# 4_-_Output.net
KiCad netlist of a schematic drawn in Altium Designer
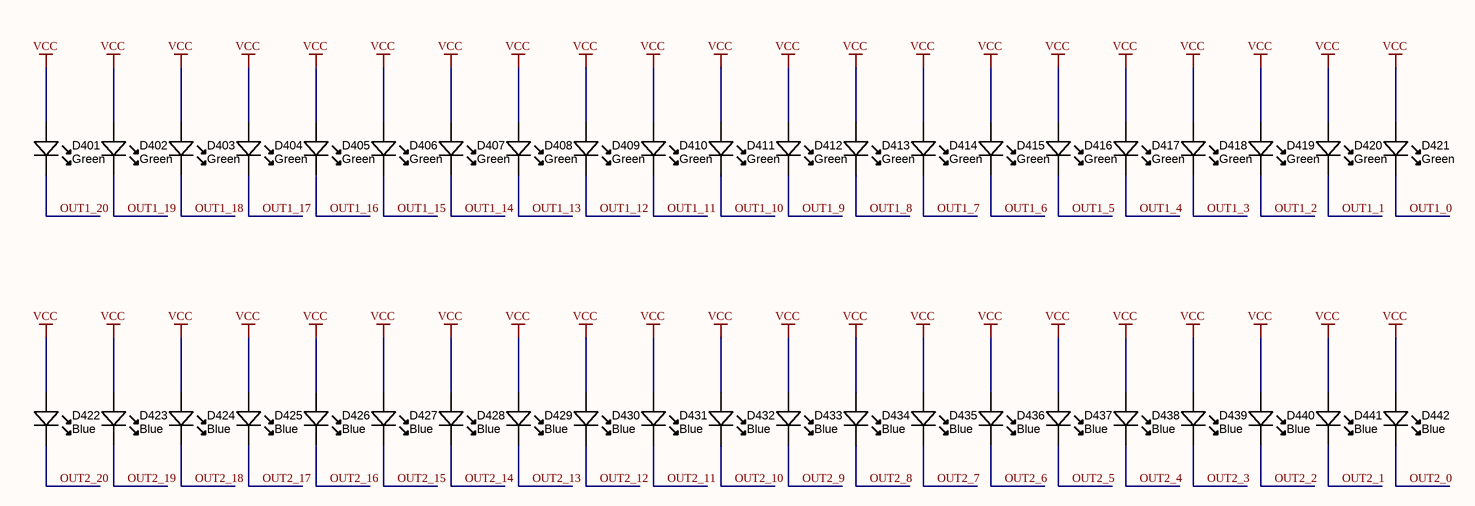
[diagram p0: 4 - Output.SchDoc]

(export (version "E")
  (design (tool "Eeschema 10.0.6"))
  (components
    (comp (ref "D401")
      (value "Green")
      (footprint "LED-0805S-SIDELED-2.1X0.6X1.0")
      (description "LED 0805 SIDELED SMD Green 250mcd 525nm")
      (fields (field (name "COLOR") "Green"))
      (libsource (lib "PBL - Light Sources") (part "LED_SMD_PureGreen_0805RA_250mcd"))
    )
    (comp (ref "D402")
      (value "Green")
      (footprint "LED-0805S-SIDELED-2.1X0.6X1.0")
      (description "LED 0805 SIDELED SMD Green 250mcd 525nm")
      (fields (field (name "COLOR") "Green"))
      (libsource (lib "PBL - Light Sources") (part "LED_SMD_PureGreen_0805RA_250mcd"))
    )
    (comp (ref "D403")
      (value "Green")
      (footprint "LED-0805S-SIDELED-2.1X0.6X1.0")
      (description "LED 0805 SIDELED SMD Green 250mcd 525nm")
      (fields (field (name "COLOR") "Green"))
      (libsource (lib "PBL - Light Sources") (part "LED_SMD_PureGreen_0805RA_250mcd"))
    )
    (comp (ref "D404")
      (value "Green")
      (footprint "LED-0805S-SIDELED-2.1X0.6X1.0")
      (description "LED 0805 SIDELED SMD Green 250mcd 525nm")
      (fields (field (name "COLOR") "Green"))
      (libsource (lib "PBL - Light Sources") (part "LED_SMD_PureGreen_0805RA_250mcd"))
    )
    (comp (ref "D405")
      (value "Green")
      (footprint "LED-0805S-SIDELED-2.1X0.6X1.0")
      (description "LED 0805 SIDELED SMD Green 250mcd 525nm")
      (fields (field (name "COLOR") "Green"))
      (libsource (lib "PBL - Light Sources") (part "LED_SMD_PureGreen_0805RA_250mcd"))
    )
    (comp (ref "D406")
      (value "Green")
      (footprint "LED-0805S-SIDELED-2.1X0.6X1.0")
      (description "LED 0805 SIDELED SMD Green 250mcd 525nm")
      (fields (field (name "COLOR") "Green"))
      (libsource (lib "PBL - Light Sources") (part "LED_SMD_PureGreen_0805RA_250mcd"))
    )
    (comp (ref "D407")
      (value "Green")
      (footprint "LED-0805S-SIDELED-2.1X0.6X1.0")
      (description "LED 0805 SIDELED SMD Green 250mcd 525nm")
      (fields (field (name "COLOR") "Green"))
      (libsource (lib "PBL - Light Sources") (part "LED_SMD_PureGreen_0805RA_250mcd"))
    )
    (comp (ref "D408")
      (value "Green")
      (footprint "LED-0805S-SIDELED-2.1X0.6X1.0")
      (description "LED 0805 SIDELED SMD Green 250mcd 525nm")
      (fields (field (name "COLOR") "Green"))
      (libsource (lib "PBL - Light Sources") (part "LED_SMD_PureGreen_0805RA_250mcd"))
    )
    (comp (ref "D409")
      (value "Green")
      (footprint "LED-0805S-SIDELED-2.1X0.6X1.0")
      (description "LED 0805 SIDELED SMD Green 250mcd 525nm")
      (fields (field (name "COLOR") "Green"))
      (libsource (lib "PBL - Light Sources") (part "LED_SMD_PureGreen_0805RA_250mcd"))
    )
    (comp (ref "D410")
      (value "Green")
      (footprint "LED-0805S-SIDELED-2.1X0.6X1.0")
      (description "LED 0805 SIDELED SMD Green 250mcd 525nm")
      (fields (field (name "COLOR") "Green"))
      (libsource (lib "PBL - Light Sources") (part "LED_SMD_PureGreen_0805RA_250mcd"))
    )
    (comp (ref "D411")
      (value "Green")
      (footprint "LED-0805S-SIDELED-2.1X0.6X1.0")
      (description "LED 0805 SIDELED SMD Green 250mcd 525nm")
      (fields (field (name "COLOR") "Green"))
      (libsource (lib "PBL - Light Sources") (part "LED_SMD_PureGreen_0805RA_250mcd"))
    )
    (comp (ref "D412")
      (value "Green")
      (footprint "LED-0805S-SIDELED-2.1X0.6X1.0")
      (description "LED 0805 SIDELED SMD Green 250mcd 525nm")
      (fields (field (name "COLOR") "Green"))
      (libsource (lib "PBL - Light Sources") (part "LED_SMD_PureGreen_0805RA_250mcd"))
    )
    (comp (ref "D413")
      (value "Green")
      (footprint "LED-0805S-SIDELED-2.1X0.6X1.0")
      (description "LED 0805 SIDELED SMD Green 250mcd 525nm")
      (fields (field (name "COLOR") "Green"))
      (libsource (lib "PBL - Light Sources") (part "LED_SMD_PureGreen_0805RA_250mcd"))
    )
    (comp (ref "D414")
      (value "Green")
      (footprint "LED-0805S-SIDELED-2.1X0.6X1.0")
      (description "LED 0805 SIDELED SMD Green 250mcd 525nm")
      (fields (field (name "COLOR") "Green"))
      (libsource (lib "PBL - Light Sources") (part "LED_SMD_PureGreen_0805RA_250mcd"))
    )
    (comp (ref "D415")
      (value "Green")
      (footprint "LED-0805S-SIDELED-2.1X0.6X1.0")
      (description "LED 0805 SIDELED SMD Green 250mcd 525nm")
      (fields (field (name "COLOR") "Green"))
      (libsource (lib "PBL - Light Sources") (part "LED_SMD_PureGreen_0805RA_250mcd"))
    )
    (comp (ref "D416")
      (value "Green")
      (footprint "LED-0805S-SIDELED-2.1X0.6X1.0")
      (description "LED 0805 SIDELED SMD Green 250mcd 525nm")
      (fields (field (name "COLOR") "Green"))
      (libsource (lib "PBL - Light Sources") (part "LED_SMD_PureGreen_0805RA_250mcd"))
    )
    (comp (ref "D417")
      (value "Green")
      (footprint "LED-0805S-SIDELED-2.1X0.6X1.0")
      (description "LED 0805 SIDELED SMD Green 250mcd 525nm")
      (fields (field (name "COLOR") "Green"))
      (libsource (lib "PBL - Light Sources") (part "LED_SMD_PureGreen_0805RA_250mcd"))
    )
    (comp (ref "D418")
      (value "Green")
      (footprint "LED-0805S-SIDELED-2.1X0.6X1.0")
      (description "LED 0805 SIDELED SMD Green 250mcd 525nm")
      (fields (field (name "COLOR") "Green"))
      (libsource (lib "PBL - Light Sources") (part "LED_SMD_PureGreen_0805RA_250mcd"))
    )
    (comp (ref "D419")
      (value "Green")
      (footprint "LED-0805S-SIDELED-2.1X0.6X1.0")
      (description "LED 0805 SIDELED SMD Green 250mcd 525nm")
      (fields (field (name "COLOR") "Green"))
      (libsource (lib "PBL - Light Sources") (part "LED_SMD_PureGreen_0805RA_250mcd"))
    )
    (comp (ref "D420")
      (value "Green")
      (footprint "LED-0805S-SIDELED-2.1X0.6X1.0")
      (description "LED 0805 SIDELED SMD Green 250mcd 525nm")
      (fields (field (name "COLOR") "Green"))
      (libsource (lib "PBL - Light Sources") (part "LED_SMD_PureGreen_0805RA_250mcd"))
    )
    (comp (ref "D421")
      (value "Green")
      (footprint "LED-0805S-SIDELED-2.1X0.6X1.0")
      (description "LED 0805 SIDELED SMD Green 250mcd 525nm")
      (fields (field (name "COLOR") "Green"))
      (libsource (lib "PBL - Light Sources") (part "LED_SMD_PureGreen_0805RA_250mcd"))
    )
    (comp (ref "D422")
      (value "Blue")
      (footprint "LED-0805S-SIDELED-2.1X0.6X1.0")
      (description "LED 0805 SIDELED SMD Green 250mcd 525nm")
      (fields (field (name "COLOR") "Blue"))
      (libsource (lib "PBL - Light Sources") (part "LED_SMD_PureGreen_0805RA_250mcd"))
    )
    (comp (ref "D423")
      (value "Blue")
      (footprint "LED-0805S-SIDELED-2.1X0.6X1.0")
      (description "LED 0805 SIDELED SMD Green 250mcd 525nm")
      (fields (field (name "COLOR") "Blue"))
      (libsource (lib "PBL - Light Sources") (part "LED_SMD_PureGreen_0805RA_250mcd"))
    )
    (comp (ref "D424")
      (value "Blue")
      (footprint "LED-0805S-SIDELED-2.1X0.6X1.0")
      (description "LED 0805 SIDELED SMD Green 250mcd 525nm")
      (fields (field (name "COLOR") "Blue"))
      (libsource (lib "PBL - Light Sources") (part "LED_SMD_PureGreen_0805RA_250mcd"))
    )
    (comp (ref "D425")
      (value "Blue")
      (footprint "LED-0805S-SIDELED-2.1X0.6X1.0")
      (description "LED 0805 SIDELED SMD Green 250mcd 525nm")
      (fields (field (name "COLOR") "Blue"))
      (libsource (lib "PBL - Light Sources") (part "LED_SMD_PureGreen_0805RA_250mcd"))
    )
    (comp (ref "D426")
      (value "Blue")
      (footprint "LED-0805S-SIDELED-2.1X0.6X1.0")
      (description "LED 0805 SIDELED SMD Green 250mcd 525nm")
      (fields (field (name "COLOR") "Blue"))
      (libsource (lib "PBL - Light Sources") (part "LED_SMD_PureGreen_0805RA_250mcd"))
    )
    (comp (ref "D427")
      (value "Blue")
      (footprint "LED-0805S-SIDELED-2.1X0.6X1.0")
      (description "LED 0805 SIDELED SMD Green 250mcd 525nm")
      (fields (field (name "COLOR") "Blue"))
      (libsource (lib "PBL - Light Sources") (part "LED_SMD_PureGreen_0805RA_250mcd"))
    )
    (comp (ref "D428")
      (value "Blue")
      (footprint "LED-0805S-SIDELED-2.1X0.6X1.0")
      (description "LED 0805 SIDELED SMD Green 250mcd 525nm")
      (fields (field (name "COLOR") "Blue"))
      (libsource (lib "PBL - Light Sources") (part "LED_SMD_PureGreen_0805RA_250mcd"))
    )
    (comp (ref "D429")
      (value "Blue")
      (footprint "LED-0805S-SIDELED-2.1X0.6X1.0")
      (description "LED 0805 SIDELED SMD Green 250mcd 525nm")
      (fields (field (name "COLOR") "Blue"))
      (libsource (lib "PBL - Light Sources") (part "LED_SMD_PureGreen_0805RA_250mcd"))
    )
    (comp (ref "D430")
      (value "Blue")
      (footprint "LED-0805S-SIDELED-2.1X0.6X1.0")
      (description "LED 0805 SIDELED SMD Green 250mcd 525nm")
      (fields (field (name "COLOR") "Blue"))
      (libsource (lib "PBL - Light Sources") (part "LED_SMD_PureGreen_0805RA_250mcd"))
    )
    (comp (ref "D431")
      (value "Blue")
      (footprint "LED-0805S-SIDELED-2.1X0.6X1.0")
      (description "LED 0805 SIDELED SMD Green 250mcd 525nm")
      (fields (field (name "COLOR") "Blue"))
      (libsource (lib "PBL - Light Sources") (part "LED_SMD_PureGreen_0805RA_250mcd"))
    )
    (comp (ref "D432")
      (value "Blue")
      (footprint "LED-0805S-SIDELED-2.1X0.6X1.0")
      (description "LED 0805 SIDELED SMD Green 250mcd 525nm")
      (fields (field (name "COLOR") "Blue"))
      (libsource (lib "PBL - Light Sources") (part "LED_SMD_PureGreen_0805RA_250mcd"))
    )
    (comp (ref "D433")
      (value "Blue")
      (footprint "LED-0805S-SIDELED-2.1X0.6X1.0")
      (description "LED 0805 SIDELED SMD Green 250mcd 525nm")
      (fields (field (name "COLOR") "Blue"))
      (libsource (lib "PBL - Light Sources") (part "LED_SMD_PureGreen_0805RA_250mcd"))
    )
    (comp (ref "D434")
      (value "Blue")
      (footprint "LED-0805S-SIDELED-2.1X0.6X1.0")
      (description "LED 0805 SIDELED SMD Green 250mcd 525nm")
      (fields (field (name "COLOR") "Blue"))
      (libsource (lib "PBL - Light Sources") (part "LED_SMD_PureGreen_0805RA_250mcd"))
    )
    (comp (ref "D435")
      (value "Blue")
      (footprint "LED-0805S-SIDELED-2.1X0.6X1.0")
      (description "LED 0805 SIDELED SMD Green 250mcd 525nm")
      (fields (field (name "COLOR") "Blue"))
      (libsource (lib "PBL - Light Sources") (part "LED_SMD_PureGreen_0805RA_250mcd"))
    )
    (comp (ref "D436")
      (value "Blue")
      (footprint "LED-0805S-SIDELED-2.1X0.6X1.0")
      (description "LED 0805 SIDELED SMD Green 250mcd 525nm")
      (fields (field (name "COLOR") "Blue"))
      (libsource (lib "PBL - Light Sources") (part "LED_SMD_PureGreen_0805RA_250mcd"))
    )
    (comp (ref "D437")
      (value "Blue")
      (footprint "LED-0805S-SIDELED-2.1X0.6X1.0")
      (description "LED 0805 SIDELED SMD Green 250mcd 525nm")
      (fields (field (name "COLOR") "Blue"))
      (libsource (lib "PBL - Light Sources") (part "LED_SMD_PureGreen_0805RA_250mcd"))
    )
    (comp (ref "D438")
      (value "Blue")
      (footprint "LED-0805S-SIDELED-2.1X0.6X1.0")
      (description "LED 0805 SIDELED SMD Green 250mcd 525nm")
      (fields (field (name "COLOR") "Blue"))
      (libsource (lib "PBL - Light Sources") (part "LED_SMD_PureGreen_0805RA_250mcd"))
    )
    (comp (ref "D439")
      (value "Blue")
      (footprint "LED-0805S-SIDELED-2.1X0.6X1.0")
      (description "LED 0805 SIDELED SMD Green 250mcd 525nm")
      (fields (field (name "COLOR") "Blue"))
      (libsource (lib "PBL - Light Sources") (part "LED_SMD_PureGreen_0805RA_250mcd"))
    )
    (comp (ref "D440")
      (value "Blue")
      (footprint "LED-0805S-SIDELED-2.1X0.6X1.0")
      (description "LED 0805 SIDELED SMD Green 250mcd 525nm")
      (fields (field (name "COLOR") "Blue"))
      (libsource (lib "PBL - Light Sources") (part "LED_SMD_PureGreen_0805RA_250mcd"))
    )
    (comp (ref "D441")
      (value "Blue")
      (footprint "LED-0805S-SIDELED-2.1X0.6X1.0")
      (description "LED 0805 SIDELED SMD Green 250mcd 525nm")
      (fields (field (name "COLOR") "Blue"))
      (libsource (lib "PBL - Light Sources") (part "LED_SMD_PureGreen_0805RA_250mcd"))
    )
    (comp (ref "D442")
      (value "Blue")
      (footprint "LED-0805S-SIDELED-2.1X0.6X1.0")
      (description "LED 0805 SIDELED SMD Green 250mcd 525nm")
      (fields (field (name "COLOR") "Blue"))
      (libsource (lib "PBL - Light Sources") (part "LED_SMD_PureGreen_0805RA_250mcd"))
    )
  )
  (nets
    (net (code "1") (name "/OUT1_0") (class "Default")
      (node (ref "D421") (pin "K") (pinfunction "K_K") (pintype "passive"))
    )
    (net (code "2") (name "/OUT1_1") (class "Default")
      (node (ref "D420") (pin "K") (pinfunction "K_K") (pintype "passive"))
    )
    (net (code "3") (name "/OUT1_2") (class "Default")
      (node (ref "D419") (pin "K") (pinfunction "K_K") (pintype "passive"))
    )
    (net (code "4") (name "/OUT1_3") (class "Default")
      (node (ref "D418") (pin "K") (pinfunction "K_K") (pintype "passive"))
    )
    (net (code "5") (name "/OUT1_4") (class "Default")
      (node (ref "D417") (pin "K") (pinfunction "K_K") (pintype "passive"))
    )
    (net (code "6") (name "/OUT1_5") (class "Default")
      (node (ref "D416") (pin "K") (pinfunction "K_K") (pintype "passive"))
    )
    (net (code "7") (name "/OUT1_6") (class "Default")
      (node (ref "D415") (pin "K") (pinfunction "K_K") (pintype "passive"))
    )
    (net (code "8") (name "/OUT1_7") (class "Default")
      (node (ref "D414") (pin "K") (pinfunction "K_K") (pintype "passive"))
    )
    (net (code "9") (name "/OUT1_8") (class "Default")
      (node (ref "D413") (pin "K") (pinfunction "K_K") (pintype "passive"))
    )
    (net (code "10") (name "/OUT1_9") (class "Default")
      (node (ref "D412") (pin "K") (pinfunction "K_K") (pintype "passive"))
    )
    (net (code "11") (name "/OUT1_10") (class "Default")
      (node (ref "D411") (pin "K") (pinfunction "K_K") (pintype "passive"))
    )
    (net (code "12") (name "/OUT1_11") (class "Default")
      (node (ref "D410") (pin "K") (pinfunction "K_K") (pintype "passive"))
    )
    (net (code "13") (name "/OUT1_12") (class "Default")
      (node (ref "D409") (pin "K") (pinfunction "K_K") (pintype "passive"))
    )
    (net (code "14") (name "/OUT1_13") (class "Default")
      (node (ref "D408") (pin "K") (pinfunction "K_K") (pintype "passive"))
    )
    (net (code "15") (name "/OUT1_14") (class "Default")
      (node (ref "D407") (pin "K") (pinfunction "K_K") (pintype "passive"))
    )
    (net (code "16") (name "/OUT1_15") (class "Default")
      (node (ref "D406") (pin "K") (pinfunction "K_K") (pintype "passive"))
    )
    (net (code "17") (name "/OUT1_16") (class "Default")
      (node (ref "D405") (pin "K") (pinfunction "K_K") (pintype "passive"))
    )
    (net (code "18") (name "/OUT1_17") (class "Default")
      (node (ref "D404") (pin "K") (pinfunction "K_K") (pintype "passive"))
    )
    (net (code "19") (name "/OUT1_18") (class "Default")
      (node (ref "D403") (pin "K") (pinfunction "K_K") (pintype "passive"))
    )
    (net (code "20") (name "/OUT1_19") (class "Default")
      (node (ref "D402") (pin "K") (pinfunction "K_K") (pintype "passive"))
    )
    (net (code "21") (name "/OUT1_20") (class "Default")
      (node (ref "D401") (pin "K") (pinfunction "K_K") (pintype "passive"))
    )
    (net (code "22") (name "/OUT2_0") (class "Default")
      (node (ref "D442") (pin "K") (pinfunction "K_K") (pintype "passive"))
    )
    (net (code "23") (name "/OUT2_1") (class "Default")
      (node (ref "D441") (pin "K") (pinfunction "K_K") (pintype "passive"))
    )
    (net (code "24") (name "/OUT2_2") (class "Default")
      (node (ref "D440") (pin "K") (pinfunction "K_K") (pintype "passive"))
    )
    (net (code "25") (name "/OUT2_3") (class "Default")
      (node (ref "D439") (pin "K") (pinfunction "K_K") (pintype "passive"))
    )
    (net (code "26") (name "/OUT2_4") (class "Default")
      (node (ref "D438") (pin "K") (pinfunction "K_K") (pintype "passive"))
    )
    (net (code "27") (name "/OUT2_5") (class "Default")
      (node (ref "D437") (pin "K") (pinfunction "K_K") (pintype "passive"))
    )
    (net (code "28") (name "/OUT2_6") (class "Default")
      (node (ref "D436") (pin "K") (pinfunction "K_K") (pintype "passive"))
    )
    (net (code "29") (name "/OUT2_7") (class "Default")
      (node (ref "D435") (pin "K") (pinfunction "K_K") (pintype "passive"))
    )
    (net (code "30") (name "/OUT2_8") (class "Default")
      (node (ref "D434") (pin "K") (pinfunction "K_K") (pintype "passive"))
    )
    (net (code "31") (name "/OUT2_9") (class "Default")
      (node (ref "D433") (pin "K") (pinfunction "K_K") (pintype "passive"))
    )
    (net (code "32") (name "/OUT2_10") (class "Default")
      (node (ref "D432") (pin "K") (pinfunction "K_K") (pintype "passive"))
    )
    (net (code "33") (name "/OUT2_11") (class "Default")
      (node (ref "D431") (pin "K") (pinfunction "K_K") (pintype "passive"))
    )
    (net (code "34") (name "/OUT2_12") (class "Default")
      (node (ref "D430") (pin "K") (pinfunction "K_K") (pintype "passive"))
    )
    (net (code "35") (name "/OUT2_13") (class "Default")
      (node (ref "D429") (pin "K") (pinfunction "K_K") (pintype "passive"))
    )
    (net (code "36") (name "/OUT2_14") (class "Default")
      (node (ref "D428") (pin "K") (pinfunction "K_K") (pintype "passive"))
    )
    (net (code "37") (name "/OUT2_15") (class "Default")
      (node (ref "D427") (pin "K") (pinfunction "K_K") (pintype "passive"))
    )
    (net (code "38") (name "/OUT2_16") (class "Default")
      (node (ref "D426") (pin "K") (pinfunction "K_K") (pintype "passive"))
    )
    (net (code "39") (name "/OUT2_17") (class "Default")
      (node (ref "D425") (pin "K") (pinfunction "K_K") (pintype "passive"))
    )
    (net (code "40") (name "/OUT2_18") (class "Default")
      (node (ref "D424") (pin "K") (pinfunction "K_K") (pintype "passive"))
    )
    (net (code "41") (name "/OUT2_19") (class "Default")
      (node (ref "D423") (pin "K") (pinfunction "K_K") (pintype "passive"))
    )
    (net (code "42") (name "/OUT2_20") (class "Default")
      (node (ref "D422") (pin "K") (pinfunction "K_K") (pintype "passive"))
    )
    (net (code "43") (name "VCC") (class "Default")
      (node (ref "D401") (pin "A") (pinfunction "A_A") (pintype "passive"))
      (node (ref "D402") (pin "A") (pinfunction "A_A") (pintype "passive"))
      (node (ref "D403") (pin "A") (pinfunction "A_A") (pintype "passive"))
      (node (ref "D404") (pin "A") (pinfunction "A_A") (pintype "passive"))
      (node (ref "D405") (pin "A") (pinfunction "A_A") (pintype "passive"))
      (node (ref "D406") (pin "A") (pinfunction "A_A") (pintype "passive"))
      (node (ref "D407") (pin "A") (pinfunction "A_A") (pintype "passive"))
      (node (ref "D408") (pin "A") (pinfunction "A_A") (pintype "passive"))
      (node (ref "D409") (pin "A") (pinfunction "A_A") (pintype "passive"))
      (node (ref "D410") (pin "A") (pinfunction "A_A") (pintype "passive"))
      (node (ref "D411") (pin "A") (pinfunction "A_A") (pintype "passive"))
      (node (ref "D412") (pin "A") (pinfunction "A_A") (pintype "passive"))
      (node (ref "D413") (pin "A") (pinfunction "A_A") (pintype "passive"))
      (node (ref "D414") (pin "A") (pinfunction "A_A") (pintype "passive"))
      (node (ref "D415") (pin "A") (pinfunction "A_A") (pintype "passive"))
      (node (ref "D416") (pin "A") (pinfunction "A_A") (pintype "passive"))
      (node (ref "D417") (pin "A") (pinfunction "A_A") (pintype "passive"))
      (node (ref "D418") (pin "A") (pinfunction "A_A") (pintype "passive"))
      (node (ref "D419") (pin "A") (pinfunction "A_A") (pintype "passive"))
      (node (ref "D420") (pin "A") (pinfunction "A_A") (pintype "passive"))
      (node (ref "D421") (pin "A") (pinfunction "A_A") (pintype "passive"))
      (node (ref "D422") (pin "A") (pinfunction "A_A") (pintype "passive"))
      (node (ref "D423") (pin "A") (pinfunction "A_A") (pintype "passive"))
      (node (ref "D424") (pin "A") (pinfunction "A_A") (pintype "passive"))
      (node (ref "D425") (pin "A") (pinfunction "A_A") (pintype "passive"))
      (node (ref "D426") (pin "A") (pinfunction "A_A") (pintype "passive"))
      (node (ref "D427") (pin "A") (pinfunction "A_A") (pintype "passive"))
      (node (ref "D428") (pin "A") (pinfunction "A_A") (pintype "passive"))
      (node (ref "D429") (pin "A") (pinfunction "A_A") (pintype "passive"))
      (node (ref "D430") (pin "A") (pinfunction "A_A") (pintype "passive"))
      (node (ref "D431") (pin "A") (pinfunction "A_A") (pintype "passive"))
      (node (ref "D432") (pin "A") (pinfunction "A_A") (pintype "passive"))
      (node (ref "D433") (pin "A") (pinfunction "A_A") (pintype "passive"))
      (node (ref "D434") (pin "A") (pinfunction "A_A") (pintype "passive"))
      (node (ref "D435") (pin "A") (pinfunction "A_A") (pintype "passive"))
      (node (ref "D436") (pin "A") (pinfunction "A_A") (pintype "passive"))
      (node (ref "D437") (pin "A") (pinfunction "A_A") (pintype "passive"))
      (node (ref "D438") (pin "A") (pinfunction "A_A") (pintype "passive"))
      (node (ref "D439") (pin "A") (pinfunction "A_A") (pintype "passive"))
      (node (ref "D440") (pin "A") (pinfunction "A_A") (pintype "passive"))
      (node (ref "D441") (pin "A") (pinfunction "A_A") (pintype "passive"))
      (node (ref "D442") (pin "A") (pinfunction "A_A") (pintype "passive"))
    )
  )
)
